# IF_TX.net
KiCad netlist of a schematic drawn in Altium Designer
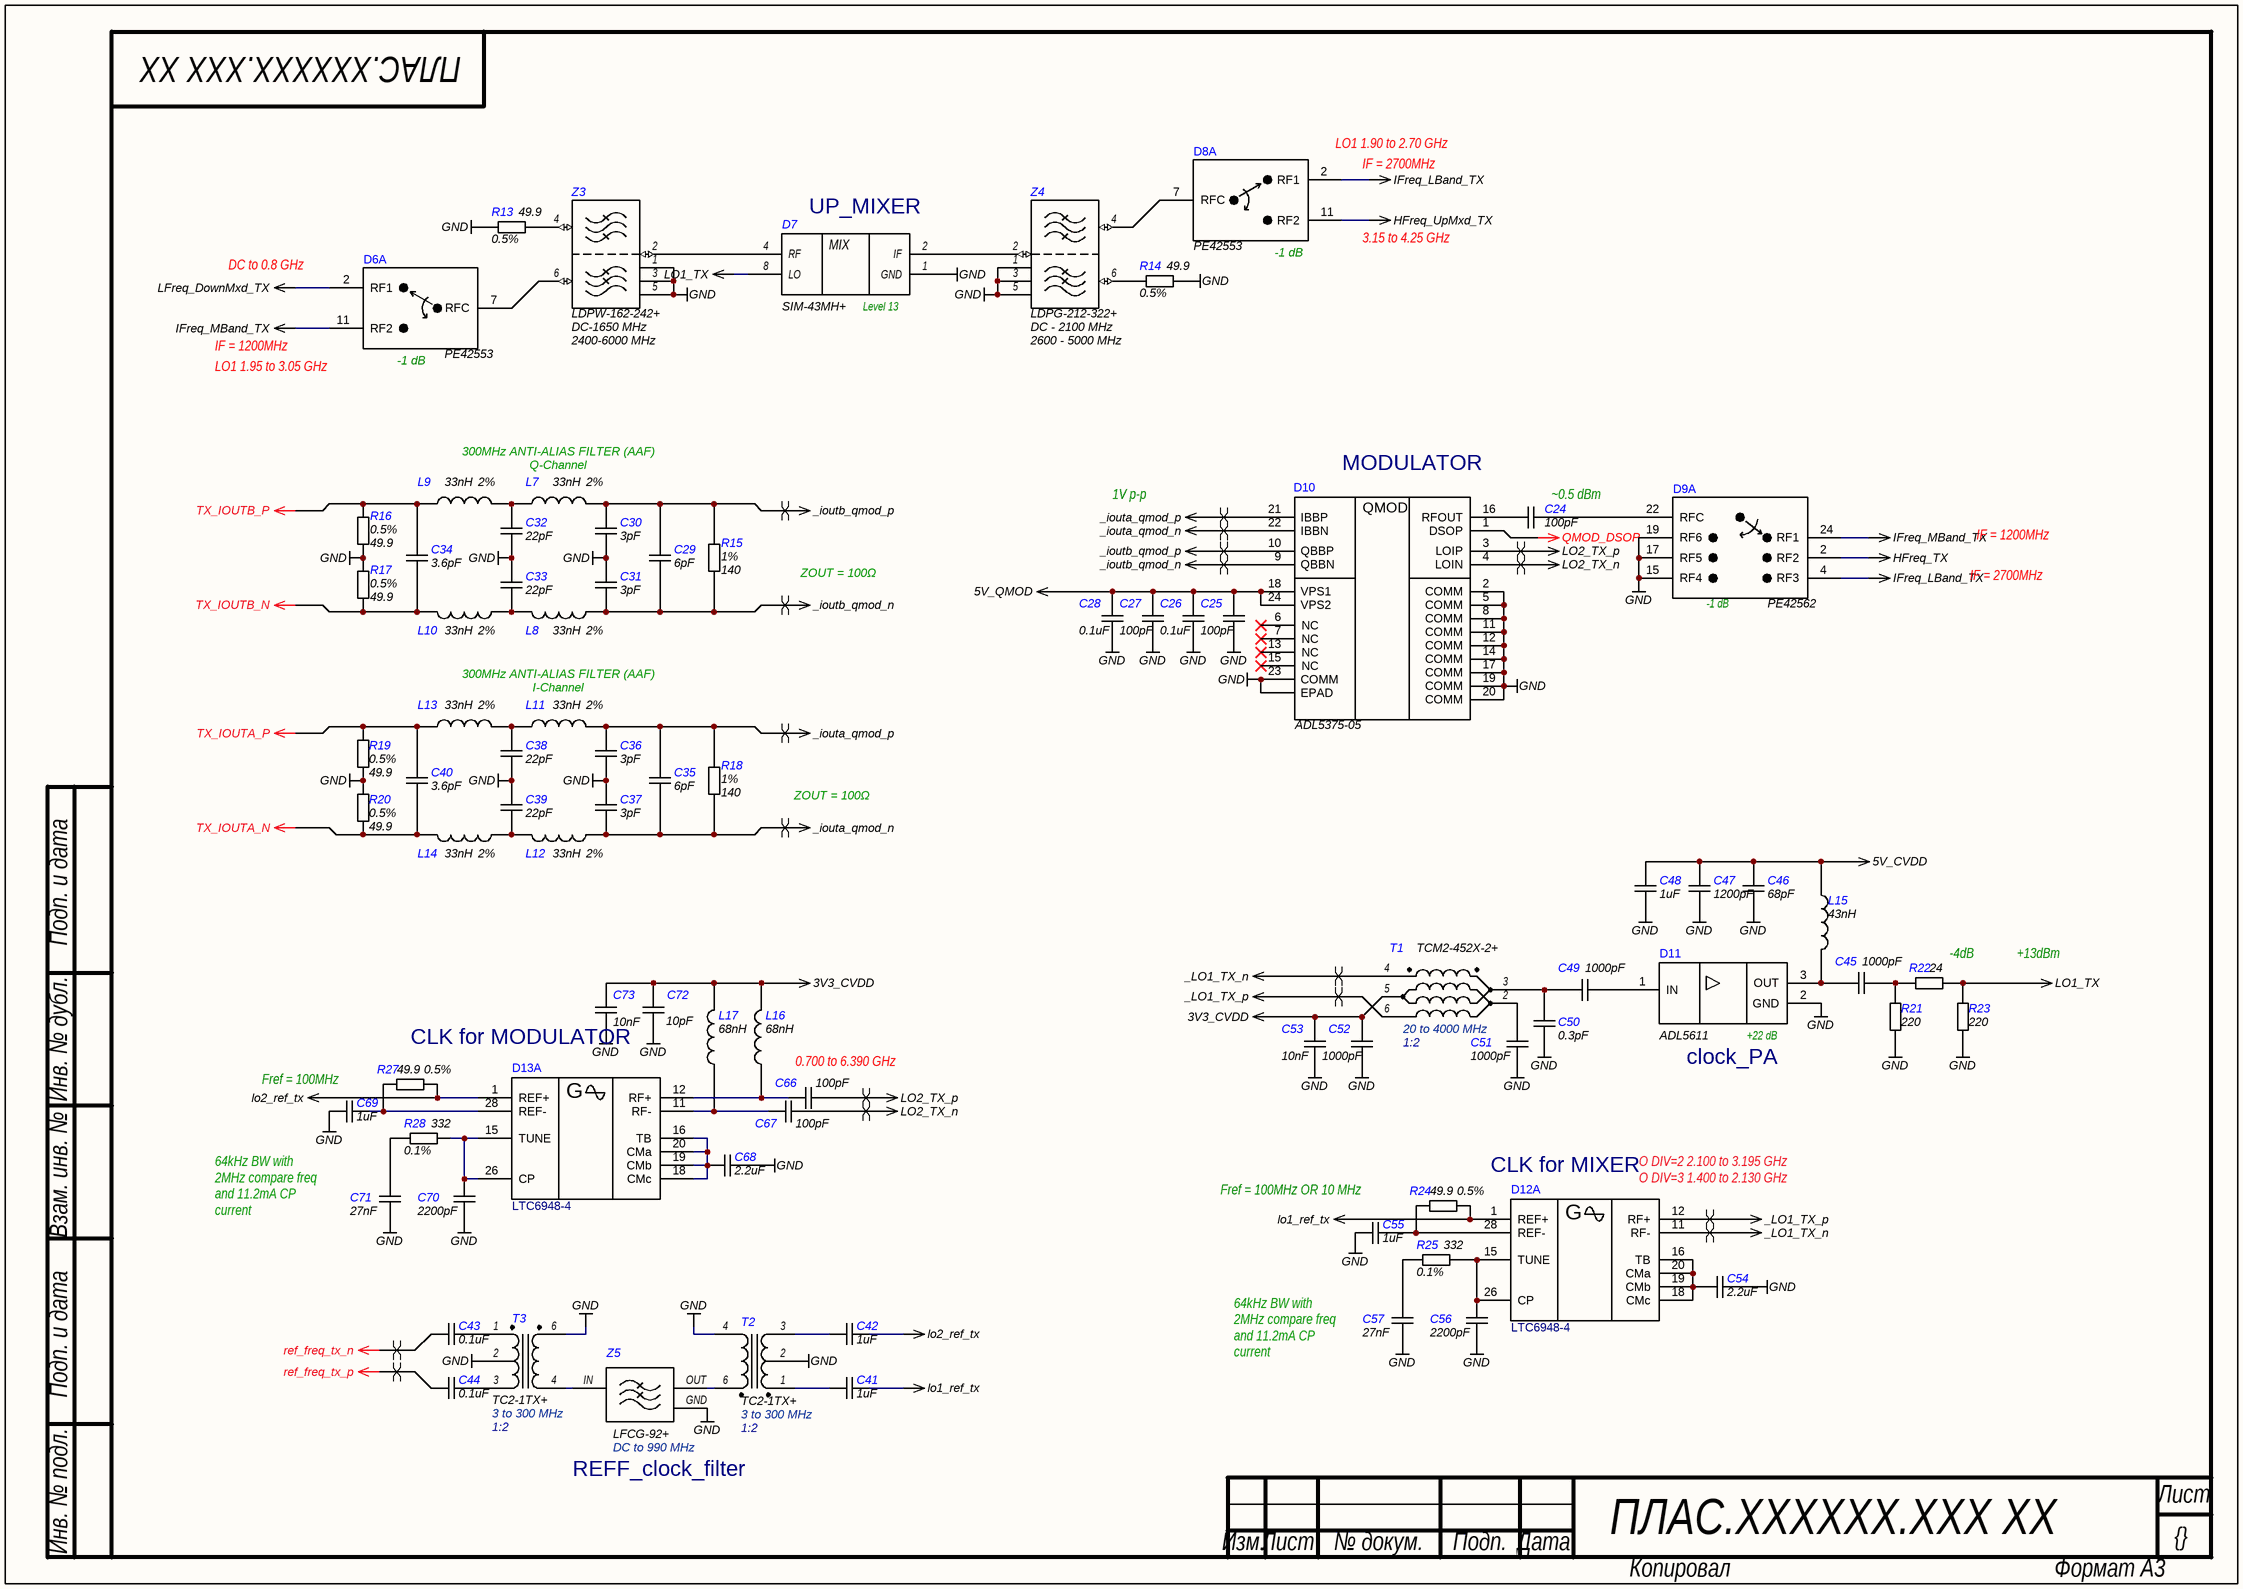
[diagram p0: IF_TX.SchDoc]

(export (version "E")
  (design (tool "Eeschema 10.0.6"))
  (components
    (comp (ref "C24")
      (value "100pF")
      (footprint "C0402")
      (description "SMD Capacitor")
      (fields (field (name "MANUFACTURER") "Murata") (field (name "TOLERANCE") "1%"))
      (libsource (lib "Kintex_SDR") (part "CAP"))
    )
    (comp (ref "C25")
      (value "100pF")
      (footprint "C0402")
      (description "SMD Capacitor")
      (fields (field (name "MANUFACTURER") "Murata") (field (name "TOLERANCE") "1%"))
      (libsource (lib "Kintex_SDR") (part "CAP"))
    )
    (comp (ref "C26")
      (value "0.1uF")
      (footprint "C0402")
      (description "SMD Capacitor")
      (fields (field (name "MANUFACTURER") "Murata") (field (name "TOLERANCE") "10%"))
      (libsource (lib "Kintex_SDR") (part "CAP"))
    )
    (comp (ref "C27")
      (value "100pF")
      (footprint "C0402")
      (description "SMD Capacitor")
      (fields (field (name "MANUFACTURER") "Murata") (field (name "TOLERANCE") "1%"))
      (libsource (lib "Kintex_SDR") (part "CAP"))
    )
    (comp (ref "C28")
      (value "0.1uF")
      (footprint "C0402")
      (description "SMD Capacitor")
      (fields (field (name "MANUFACTURER") "Murata") (field (name "TOLERANCE") "10%"))
      (libsource (lib "Kintex_SDR") (part "CAP"))
    )
    (comp (ref "C29")
      (value "6pF")
      (footprint "C0402")
      (description "SMD Capacitor")
      (fields (field (name "MANUFACTURER") "Murata") (field (name "TOLERANCE") "±0.5pF"))
      (libsource (lib "Kintex_SDR") (part "CAP"))
    )
    (comp (ref "C30")
      (value "3pF")
      (footprint "C0402")
      (description "SMD Capacitor")
      (fields (field (name "MANUFACTURER") "Murata") (field (name "TOLERANCE") "±0.25pF"))
      (libsource (lib "Kintex_SDR") (part "CAP"))
    )
    (comp (ref "C31")
      (value "3pF")
      (footprint "C0402")
      (description "SMD Capacitor")
      (fields (field (name "MANUFACTURER") "Murata") (field (name "TOLERANCE") "±0.25pF"))
      (libsource (lib "Kintex_SDR") (part "CAP"))
    )
    (comp (ref "C32")
      (value "22pF")
      (footprint "C0402")
      (description "SMD Capacitor")
      (fields (field (name "MANUFACTURER") "Murata") (field (name "TOLERANCE") "1%"))
      (libsource (lib "Kintex_SDR") (part "CAP"))
    )
    (comp (ref "C33")
      (value "22pF")
      (footprint "C0402")
      (description "SMD Capacitor")
      (fields (field (name "MANUFACTURER") "Murata") (field (name "TOLERANCE") "1%"))
      (libsource (lib "Kintex_SDR") (part "CAP"))
    )
    (comp (ref "C34")
      (value "3.6pF")
      (footprint "C0402")
      (description "SMD Capacitor")
      (fields (field (name "MANUFACTURER") "Murata") (field (name "TOLERANCE") "±0.25pF"))
      (libsource (lib "Kintex_SDR") (part "CAP"))
    )
    (comp (ref "C35")
      (value "6pF")
      (footprint "C0402")
      (description "SMD Capacitor")
      (fields (field (name "MANUFACTURER") "Murata") (field (name "TOLERANCE") "±0.5pF"))
      (libsource (lib "Kintex_SDR") (part "CAP"))
    )
    (comp (ref "C36")
      (value "3pF")
      (footprint "C0402")
      (description "SMD Capacitor")
      (fields (field (name "MANUFACTURER") "Murata") (field (name "TOLERANCE") "±0.25pF"))
      (libsource (lib "Kintex_SDR") (part "CAP"))
    )
    (comp (ref "C37")
      (value "3pF")
      (footprint "C0402")
      (description "SMD Capacitor")
      (fields (field (name "MANUFACTURER") "Murata") (field (name "TOLERANCE") "±0.25pF"))
      (libsource (lib "Kintex_SDR") (part "CAP"))
    )
    (comp (ref "C38")
      (value "22pF")
      (footprint "C0402")
      (description "SMD Capacitor")
      (fields (field (name "MANUFACTURER") "Murata") (field (name "TOLERANCE") "1%"))
      (libsource (lib "Kintex_SDR") (part "CAP"))
    )
    (comp (ref "C39")
      (value "22pF")
      (footprint "C0402")
      (description "SMD Capacitor")
      (fields (field (name "MANUFACTURER") "Murata") (field (name "TOLERANCE") "1%"))
      (libsource (lib "Kintex_SDR") (part "CAP"))
    )
    (comp (ref "C40")
      (value "3.6pF")
      (footprint "C0402")
      (description "SMD Capacitor")
      (fields (field (name "MANUFACTURER") "Murata") (field (name "TOLERANCE") "±0.25pF"))
      (libsource (lib "Kintex_SDR") (part "CAP"))
    )
    (comp (ref "C41")
      (value "1uF")
      (footprint "C0603")
      (description "SMD Capacitor")
      (fields (field (name "MANUFACTURER") "Kemet") (field (name "TOLERANCE") "10%"))
      (libsource (lib "Kintex_SDR") (part "CAP"))
    )
    (comp (ref "C42")
      (value "1uF")
      (footprint "C0603")
      (description "SMD Capacitor")
      (fields (field (name "MANUFACTURER") "Kemet") (field (name "TOLERANCE") "10%"))
      (libsource (lib "Kintex_SDR") (part "CAP"))
    )
    (comp (ref "C43")
      (value "0.1uF")
      (footprint "C0402")
      (description "SMD Capacitor")
      (fields (field (name "MANUFACTURER") "Murata") (field (name "TOLERANCE") "10%"))
      (libsource (lib "Kintex_SDR") (part "CAP"))
    )
    (comp (ref "C44")
      (value "0.1uF")
      (footprint "C0402")
      (description "SMD Capacitor")
      (fields (field (name "MANUFACTURER") "Murata") (field (name "TOLERANCE") "10%"))
      (libsource (lib "Kintex_SDR") (part "CAP"))
    )
    (comp (ref "C45")
      (value "1000pF")
      (footprint "C0402")
      (description "SMD Capacitor")
      (fields (field (name "MANUFACTURER") "Murata") (field (name "TOLERANCE") "5%"))
      (libsource (lib "Kintex_SDR") (part "CAP"))
    )
    (comp (ref "C46")
      (value "68pF")
      (footprint "C0402")
      (description "SMD Capacitor")
      (fields (field (name "MANUFACTURER") "Murata") (field (name "TOLERANCE") "±1%"))
      (libsource (lib "Kintex_SDR") (part "CAP"))
    )
    (comp (ref "C47")
      (value "1200pF")
      (footprint "C0603")
      (description "SMD Capacitor")
      (fields (field (name "MANUFACTURER") "Murata") (field (name "TOLERANCE") "±5%"))
      (libsource (lib "Kintex_SDR") (part "CAP"))
    )
    (comp (ref "C48")
      (value "1uF")
      (footprint "C0603")
      (description "SMD Capacitor")
      (fields (field (name "MANUFACTURER") "Kemet") (field (name "TOLERANCE") "10%"))
      (libsource (lib "Kintex_SDR") (part "CAP"))
    )
    (comp (ref "C49")
      (value "1000pF")
      (footprint "C0402")
      (description "SMD Capacitor")
      (fields (field (name "MANUFACTURER") "Murata") (field (name "TOLERANCE") "5%"))
      (libsource (lib "Kintex_SDR") (part "CAP"))
    )
    (comp (ref "C50")
      (value "0.3pF")
      (footprint "C0402")
      (description "SMD Capacitor")
      (fields (field (name "MANUFACTURER") "Murata") (field (name "TOLERANCE") "±0.05pF"))
      (libsource (lib "Kintex_SDR") (part "CAP"))
    )
    (comp (ref "C51")
      (value "1000pF")
      (footprint "C0402")
      (description "SMD Capacitor")
      (fields (field (name "MANUFACTURER") "Murata") (field (name "TOLERANCE") "5%"))
      (libsource (lib "Kintex_SDR") (part "CAP"))
    )
    (comp (ref "C52")
      (value "1000pF")
      (footprint "C0402")
      (description "SMD Capacitor")
      (fields (field (name "MANUFACTURER") "Murata") (field (name "TOLERANCE") "5%"))
      (libsource (lib "Kintex_SDR") (part "CAP"))
    )
    (comp (ref "C53")
      (value "10nF")
      (footprint "C0402")
      (description "SMD Capacitor")
      (fields (field (name "MANUFACTURER") "Murata") (field (name "TOLERANCE") "10%"))
      (libsource (lib "Kintex_SDR") (part "CAP"))
    )
    (comp (ref "C54")
      (value "2.2uF")
      (footprint "C0603")
      (description "SMD Capacitor")
      (fields (field (name "MANUFACTURER") "Murata") (field (name "TOLERANCE") "10%"))
      (libsource (lib "Kintex_SDR") (part "CAP"))
    )
    (comp (ref "C55")
      (value "1uF")
      (footprint "C0603")
      (description "SMD Capacitor")
      (fields (field (name "MANUFACTURER") "Kemet") (field (name "TOLERANCE") "10%"))
      (libsource (lib "Kintex_SDR") (part "CAP"))
    )
    (comp (ref "C56")
      (value "2200pF")
      (footprint "C0603")
      (description "SMD Capacitor")
      (fields (field (name "MANUFACTURER") "Kemet") (field (name "TOLERANCE") "1%"))
      (libsource (lib "Kintex_SDR") (part "CAP"))
    )
    (comp (ref "C57")
      (value "27nF")
      (footprint "C0603")
      (description "SMD Capacitor")
      (fields (field (name "MANUFACTURER") "KYOCERA AVX") (field (name "TOLERANCE") "±5%"))
      (libsource (lib "Kintex_SDR") (part "CAP"))
    )
    (comp (ref "C66")
      (value "100pF")
      (footprint "C0402")
      (description "SMD Capacitor")
      (fields (field (name "MANUFACTURER") "Murata") (field (name "TOLERANCE") "1%"))
      (libsource (lib "Kintex_SDR") (part "CAP"))
    )
    (comp (ref "C67")
      (value "100pF")
      (footprint "C0402")
      (description "SMD Capacitor")
      (fields (field (name "MANUFACTURER") "Murata") (field (name "TOLERANCE") "1%"))
      (libsource (lib "Kintex_SDR") (part "CAP"))
    )
    (comp (ref "C68")
      (value "2.2uF")
      (footprint "C0603")
      (description "SMD Capacitor")
      (fields (field (name "MANUFACTURER") "Murata") (field (name "TOLERANCE") "10%"))
      (libsource (lib "Kintex_SDR") (part "CAP"))
    )
    (comp (ref "C69")
      (value "1uF")
      (footprint "C0603")
      (description "SMD Capacitor")
      (fields (field (name "MANUFACTURER") "Kemet") (field (name "TOLERANCE") "10%"))
      (libsource (lib "Kintex_SDR") (part "CAP"))
    )
    (comp (ref "C70")
      (value "2200pF")
      (footprint "C0603")
      (description "SMD Capacitor")
      (fields (field (name "MANUFACTURER") "Kemet") (field (name "TOLERANCE") "1%"))
      (libsource (lib "Kintex_SDR") (part "CAP"))
    )
    (comp (ref "C71")
      (value "27nF")
      (footprint "C0603")
      (description "SMD Capacitor")
      (fields (field (name "MANUFACTURER") "KYOCERA AVX") (field (name "TOLERANCE") "±5%"))
      (libsource (lib "Kintex_SDR") (part "CAP"))
    )
    (comp (ref "C72")
      (value "10pF")
      (footprint "C0402")
      (description "SMD Capacitor")
      (fields (field (name "MANUFACTURER") "Murata") (field (name "TOLERANCE") "1%"))
      (libsource (lib "Kintex_SDR") (part "CAP"))
    )
    (comp (ref "C73")
      (value "10nF")
      (footprint "C0402")
      (description "SMD Capacitor")
      (fields (field (name "MANUFACTURER") "Murata") (field (name "TOLERANCE") "10%"))
      (libsource (lib "Kintex_SDR") (part "CAP"))
    )
    (comp (ref "D6")
      (value "PE42553")
      (footprint "QFN-16")
      (description "HaRPTM technology-enhanced absorptive SPDT")
      (fields (field (name "MANUFACTURER") "Peregrine Technical Solutions"))
      (libsource (lib "DBLib") (part "PE42553"))
    )
    (comp (ref "D7")
      (value "SIM-43MH+")
      (footprint "DBLib:SIM-43MH+")
      (description "Frequency Mixer")
      (fields (field (name "MANUFACTURER") "Mini-Circuits"))
      (libsource (lib "DBLib") (part "SIM-43MH+"))
    )
    (comp (ref "D8")
      (value "PE42553")
      (footprint "QFN-16")
      (description "HaRPTM technology-enhanced absorptive SPDT")
      (fields (field (name "MANUFACTURER") "Peregrine Technical Solutions"))
      (libsource (lib "") (part "PE42553_1"))
    )
    (comp (ref "D9")
      (value "PE42562")
      (footprint "QFN-24")
      (description "The PE42582 is a HaRP™ technology-enhanced absorptive SP6T RF switch")
      (fields (field (name "MANUFACTURER") "Peregrine Technical Solutions"))
      (libsource (lib "DBLib") (part "PE42562"))
    )
    (comp (ref "D10")
      (value "ADL5375")
      (footprint "LFCSP-24")
      (description "Broadband Quadrature Modulator")
      (fields
        (field (name "MANUFACTURER") "Analog Devices")
        (field (name "VOLTAGE") "4.75 V to 5.25 V")
        (field (name "NAME") "ADL5375-05")
      )
      (libsource (lib "DBLib") (part "ADL5375"))
    )
    (comp (ref "D11")
      (value "ADL5611")
      (footprint "DBLib:ADL5610")
      (description "RF/IF Gain Block")
      (fields (field (name "MANUFACTURER") "Analog Devices"))
      (libsource (lib "DBLib") (part "ADL5611"))
    )
    (comp (ref "D12")
      (value "LTC6948-4")
      (footprint "QFN-28")
      (description "The LTC®LTC6948 is a high performance, low noise, 6.39GHz  phase-locked loop (PLL)")
      (fields (field (name "MANUFACTURER") "Linear Technology") (field (name "VOLTAGE") "3.15 V ~ 5.25 V"))
      (libsource (lib "DBLib") (part "LTC6948"))
    )
    (comp (ref "D13")
      (value "LTC6948-4")
      (footprint "QFN-28")
      (description "The LTC®LTC6948 is a high performance, low noise, 6.39GHz  phase-locked loop (PLL)")
      (fields (field (name "MANUFACTURER") "Linear Technology") (field (name "VOLTAGE") "3.15 V ~ 5.25 V"))
      (libsource (lib "DBLib") (part "LTC6948"))
    )
    (comp (ref "L7")
      (value "33nH")
      (footprint "DBLib:L0603_HP")
      (description "Chip SMD Inductor")
      (fields
        (field (name "MANUFACTURER") "Coilcraft")
        (field (name "TOLERANCE") "2%")
        (field (name "Comment") "Inductor RF")
      )
      (libsource (lib "") (part "Inductor RF_1"))
    )
    (comp (ref "L8")
      (value "33nH")
      (footprint "DBLib:L0603_HP")
      (description "Chip SMD Inductor")
      (fields
        (field (name "MANUFACTURER") "Coilcraft")
        (field (name "TOLERANCE") "2%")
        (field (name "Comment") "Inductor RF")
      )
      (libsource (lib "DBLib") (part "Inductor RF"))
    )
    (comp (ref "L9")
      (value "33nH")
      (footprint "DBLib:L0603_HP")
      (description "Chip SMD Inductor")
      (fields
        (field (name "MANUFACTURER") "Coilcraft")
        (field (name "TOLERANCE") "2%")
        (field (name "Comment") "Inductor RF")
      )
      (libsource (lib "") (part "Inductor RF_1"))
    )
    (comp (ref "L10")
      (value "33nH")
      (footprint "DBLib:L0603_HP")
      (description "Chip SMD Inductor")
      (fields
        (field (name "MANUFACTURER") "Coilcraft")
        (field (name "TOLERANCE") "2%")
        (field (name "Comment") "Inductor RF")
      )
      (libsource (lib "DBLib") (part "Inductor RF"))
    )
    (comp (ref "L11")
      (value "33nH")
      (footprint "DBLib:L0603_HP")
      (description "Chip SMD Inductor")
      (fields
        (field (name "MANUFACTURER") "Coilcraft")
        (field (name "TOLERANCE") "2%")
        (field (name "Comment") "Inductor RF")
      )
      (libsource (lib "") (part "Inductor RF_1"))
    )
    (comp (ref "L12")
      (value "33nH")
      (footprint "DBLib:L0603_HP")
      (description "Chip SMD Inductor")
      (fields
        (field (name "MANUFACTURER") "Coilcraft")
        (field (name "TOLERANCE") "2%")
        (field (name "Comment") "Inductor RF")
      )
      (libsource (lib "DBLib") (part "Inductor RF"))
    )
    (comp (ref "L13")
      (value "33nH")
      (footprint "DBLib:L0603_HP")
      (description "Chip SMD Inductor")
      (fields
        (field (name "MANUFACTURER") "Coilcraft")
        (field (name "TOLERANCE") "2%")
        (field (name "Comment") "Inductor RF")
      )
      (libsource (lib "") (part "Inductor RF_1"))
    )
    (comp (ref "L14")
      (value "33nH")
      (footprint "DBLib:L0603_HP")
      (description "Chip SMD Inductor")
      (fields
        (field (name "MANUFACTURER") "Coilcraft")
        (field (name "TOLERANCE") "2%")
        (field (name "Comment") "Inductor RF")
      )
      (libsource (lib "DBLib") (part "Inductor RF"))
    )
    (comp (ref "L15")
      (value "43nH")
      (footprint "DBLib:L0603_HP")
      (description "Chip SMD Inductor")
      (fields (field (name "MANUFACTURER") "Coilcraft") (field (name "TOLERANCE") "5%"))
      (libsource (lib "DBLib") (part "Inductor RF"))
    )
    (comp (ref "L16")
      (value "68nH")
      (footprint "DBLib:L0603_HP")
      (description "Chip SMD Inductor")
      (fields (field (name "MANUFACTURER") "Coilcraft") (field (name "TOLERANCE") "5%"))
      (libsource (lib "") (part "Inductor RF_1"))
    )
    (comp (ref "L17")
      (value "68nH")
      (footprint "DBLib:L0603_HP")
      (description "Chip SMD Inductor")
      (fields (field (name "MANUFACTURER") "Coilcraft") (field (name "TOLERANCE") "5%"))
      (libsource (lib "") (part "Inductor RF_1"))
    )
    (comp (ref "R13")
      (value "49.9")
      (footprint "R0402")
      (description "SMD Resistor")
      (fields
        (field (name "POWER") "0.063 Wt")
        (field (name "TOLERANCE") "0.5%")
        (field (name "MANUFACTURER") "Panasonic Electronic Components")
      )
      (libsource (lib "") (part "RES_2"))
    )
    (comp (ref "R14")
      (value "49.9")
      (footprint "R0402")
      (description "SMD Resistor")
      (fields
        (field (name "POWER") "0.063 Wt")
        (field (name "TOLERANCE") "0.5%")
        (field (name "MANUFACTURER") "Panasonic Electronic Components")
      )
      (libsource (lib "") (part "RES_1"))
    )
    (comp (ref "R15")
      (value "140")
      (footprint "R0402")
      (description "SMD Resistor")
      (fields
        (field (name "POWER") "0.1 Wt")
        (field (name "TOLERANCE") "1%")
        (field (name "MANUFACTURER") "Panasonic Electronic Components")
      )
      (libsource (lib "") (part "RES_1"))
    )
    (comp (ref "R16")
      (value "49.9")
      (footprint "R0402")
      (description "SMD Resistor")
      (fields
        (field (name "POWER") "0.063 Wt")
        (field (name "TOLERANCE") "0.5%")
        (field (name "MANUFACTURER") "Panasonic Electronic Components")
      )
      (libsource (lib "") (part "RES_1"))
    )
    (comp (ref "R17")
      (value "49.9")
      (footprint "R0402")
      (description "SMD Resistor")
      (fields
        (field (name "POWER") "0.063 Wt")
        (field (name "TOLERANCE") "0.5%")
        (field (name "MANUFACTURER") "Panasonic Electronic Components")
      )
      (libsource (lib "") (part "RES_1"))
    )
    (comp (ref "R18")
      (value "140")
      (footprint "R0402")
      (description "SMD Resistor")
      (fields
        (field (name "POWER") "0.1 Wt")
        (field (name "TOLERANCE") "1%")
        (field (name "MANUFACTURER") "Panasonic Electronic Components")
      )
      (libsource (lib "") (part "RES_1"))
    )
    (comp (ref "R19")
      (value "49.9")
      (footprint "R0402")
      (description "SMD Resistor")
      (fields
        (field (name "POWER") "0.063 Wt")
        (field (name "TOLERANCE") "0.5%")
        (field (name "MANUFACTURER") "Panasonic Electronic Components")
      )
      (libsource (lib "") (part "RES_1"))
    )
    (comp (ref "R20")
      (value "49.9")
      (footprint "R0402")
      (description "SMD Resistor")
      (fields
        (field (name "POWER") "0.063 Wt")
        (field (name "TOLERANCE") "0.5%")
        (field (name "MANUFACTURER") "Panasonic Electronic Components")
      )
      (libsource (lib "") (part "RES_1"))
    )
    (comp (ref "R21")
      (value "220")
      (footprint "R0402")
      (description "SMD Resistor")
      (fields (field (name "POWER") "0.1 Wt") (field (name "TOLERANCE") "±1%"))
      (libsource (lib "Kintex_SDR") (part "RES"))
    )
    (comp (ref "R22")
      (value "24")
      (footprint "R0402")
      (description "SMD Resistor")
      (fields (field (name "POWER") "0.063 Wt") (field (name "TOLERANCE") "±1%"))
      (libsource (lib "") (part "RES_1"))
    )
    (comp (ref "R23")
      (value "220")
      (footprint "R0402")
      (description "SMD Resistor")
      (fields (field (name "POWER") "0.1 Wt") (field (name "TOLERANCE") "±1%"))
      (libsource (lib "Kintex_SDR") (part "RES"))
    )
    (comp (ref "R24")
      (value "49.9")
      (footprint "R0402")
      (description "SMD Resistor")
      (fields
        (field (name "POWER") "0.063 Wt")
        (field (name "TOLERANCE") "0.5%")
        (field (name "MANUFACTURER") "Panasonic Electronic Components")
      )
      (libsource (lib "") (part "RES_1"))
    )
    (comp (ref "R25")
      (value "332")
      (footprint "R0603")
      (description "SMD Resistor")
      (fields
        (field (name "POWER") "0.1 Wt")
        (field (name "TOLERANCE") "0.1%")
        (field (name "MANUFACTURER") "Panasonic Electronic Components")
      )
      (libsource (lib "") (part "RES_1"))
    )
    (comp (ref "R27")
      (value "49.9")
      (footprint "R0402")
      (description "SMD Resistor")
      (fields
        (field (name "POWER") "0.063 Wt")
        (field (name "TOLERANCE") "0.5%")
        (field (name "MANUFACTURER") "Panasonic Electronic Components")
      )
      (libsource (lib "") (part "RES_1"))
    )
    (comp (ref "R28")
      (value "332")
      (footprint "R0603")
      (description "SMD Resistor")
      (fields
        (field (name "POWER") "0.1 Wt")
        (field (name "TOLERANCE") "0.1%")
        (field (name "MANUFACTURER") "Panasonic Electronic Components")
      )
      (libsource (lib "") (part "RES_1"))
    )
    (comp (ref "T1")
      (value "TCM2-452X-2+")
      (footprint "DB1627")
      (description "RF Transformer")
      (fields
        (field (name "MANUFACTURER") "Mini-Circuits")
        (field (name "FREQUENCY") "20 to 4000 MHz")
        (field (name "RATIO") "1:2")
      )
      (libsource (lib "DBLib") (part "TCM2-452X-2+"))
    )
    (comp (ref "T2")
      (value "TC2-1TX+")
      (footprint "DBLib:AT1521")
      (description "RF Transformer")
      (fields
        (field (name "MANUFACTURER") "Mini-Circuits")
        (field (name "FREQUENCY") "3 to 300 MHz")
        (field (name "RATIO") "1:2")
      )
      (libsource (lib "DBLib") (part "TC2-1TX+"))
    )
    (comp (ref "T3")
      (value "TC2-1TX+")
      (footprint "DBLib:AT1521")
      (description "RF Transformer")
      (fields
        (field (name "MANUFACTURER") "Mini-Circuits")
        (field (name "FREQUENCY") "3 to 300 MHz")
        (field (name "RATIO") "1:2")
      )
      (libsource (lib "DBLib") (part "TC2-1TX+"))
    )
    (comp (ref "Z3")
      (value "LDPW-162-242+")
      (footprint "DBLib:JC0603C")
      (description "Diplexer")
      (fields
        (field (name "MANUFACTURER") "Mini-Circuits")
        (field (name "LOW PASS") "DC-1650 MHz")
        (field (name "HIGH PASS") "2400-6000 MHz")
      )
      (libsource (lib "DBLib") (part "LDPW-162-242+"))
    )
    (comp (ref "Z4")
      (value "LDPG-212-322+")
      (footprint "GE0805C-10")
      (description "Diplexer")
      (fields
        (field (name "MANUFACTURER") "Mini-Circuits")
        (field (name "LOW PASS") "DC - 2100 MHz")
        (field (name "HIGH PASS") "2600 - 5000 MHz")
      )
      (libsource (lib "DBLib") (part "LDPG-212-322+"))
    )
    (comp (ref "Z5")
      (value "LFCG-92+")
      (footprint "GE0805C-2")
      (description "Low Pass Filter")
      (fields (field (name "MANUFACTURER") "Mini-Circuits") (field (name "FREQUENCY") "DC to 990 MHz"))
      (libsource (lib "DBLib") (part "LFCG-92+"))
    )
  )
  (nets
    (net (code "1") (name "3V3_CVDD") (class "Default")
      (node (ref "C52") (pin "1") (pinfunction "1_1") (pintype "passive"))
      (node (ref "C53") (pin "2") (pinfunction "2_2") (pintype "passive"))
      (node (ref "C72") (pin "2") (pinfunction "2_2") (pintype "passive"))
      (node (ref "C73") (pin "2") (pinfunction "2_2") (pintype "passive"))
      (node (ref "L16") (pin "2") (pinfunction "2_2") (pintype "passive"))
      (node (ref "L17") (pin "2") (pinfunction "2_2") (pintype "passive"))
      (node (ref "T1") (pin "5") (pinfunction "5_5") (pintype "passive"))
    )
    (net (code "2") (name "5V_CVDD") (class "Default")
      (node (ref "C46") (pin "2") (pinfunction "2_2") (pintype "passive"))
      (node (ref "C47") (pin "2") (pinfunction "2_2") (pintype "passive"))
      (node (ref "C48") (pin "1") (pinfunction "1_1") (pintype "passive"))
      (node (ref "L15") (pin "2") (pinfunction "2_2") (pintype "passive"))
    )
    (net (code "3") (name "5V_QMOD") (class "Default")
      (node (ref "C25") (pin "2") (pinfunction "2_2") (pintype "passive"))
      (node (ref "C26") (pin "2") (pinfunction "2_2") (pintype "passive"))
      (node (ref "C27") (pin "2") (pinfunction "2_2") (pintype "passive"))
      (node (ref "C28") (pin "2") (pinfunction "2_2") (pintype "passive"))
      (node (ref "D10") (pin "18") (pinfunction "VPS1_18") (pintype "passive"))
      (node (ref "D10") (pin "24") (pinfunction "VPS2_24") (pintype "passive"))
    )
    (net (code "4") (name "GND") (class "Default")
      (node (ref "C25") (pin "1") (pinfunction "1_1") (pintype "passive"))
      (node (ref "C26") (pin "1") (pinfunction "1_1") (pintype "passive"))
      (node (ref "C27") (pin "1") (pinfunction "1_1") (pintype "passive"))
      (node (ref "C28") (pin "1") (pinfunction "1_1") (pintype "passive"))
      (node (ref "C30") (pin "2") (pinfunction "2_2") (pintype "passive"))
      (node (ref "C31") (pin "1") (pinfunction "1_1") (pintype "passive"))
      (node (ref "C32") (pin "2") (pinfunction "2_2") (pintype "passive"))
      (node (ref "C33") (pin "1") (pinfunction "1_1") (pintype "passive"))
      (node (ref "C36") (pin "2") (pinfunction "2_2") (pintype "passive"))
      (node (ref "C37") (pin "1") (pinfunction "1_1") (pintype "passive"))
      (node (ref "C38") (pin "2") (pinfunction "2_2") (pintype "passive"))
      (node (ref "C39") (pin "1") (pinfunction "1_1") (pintype "passive"))
      (node (ref "C46") (pin "1") (pinfunction "1_1") (pintype "passive"))
      (node (ref "C47") (pin "1") (pinfunction "1_1") (pintype "passive"))
      (node (ref "C48") (pin "2") (pinfunction "2_2") (pintype "passive"))
      (node (ref "C50") (pin "1") (pinfunction "1_1") (pintype "passive"))
      (node (ref "C51") (pin "2") (pinfunction "2_2") (pintype "passive"))
      (node (ref "C52") (pin "2") (pinfunction "2_2") (pintype "passive"))
      (node (ref "C53") (pin "1") (pinfunction "1_1") (pintype "passive"))
      (node (ref "C54") (pin "1") (pinfunction "1_1") (pintype "passive"))
      (node (ref "C55") (pin "2") (pinfunction "2_2") (pintype "passive"))
      (node (ref "C56") (pin "1") (pinfunction "1_1") (pintype "passive"))
      (node (ref "C57") (pin "1") (pinfunction "1_1") (pintype "passive"))
      (node (ref "C68") (pin "1") (pinfunction "1_1") (pintype "passive"))
      (node (ref "C69") (pin "2") (pinfunction "2_2") (pintype "passive"))
      (node (ref "C70") (pin "1") (pinfunction "1_1") (pintype "passive"))
      (node (ref "C71") (pin "1") (pinfunction "1_1") (pintype "passive"))
      (node (ref "C72") (pin "1") (pinfunction "1_1") (pintype "passive"))
      (node (ref "C73") (pin "1") (pinfunction "1_1") (pintype "passive"))
      (node (ref "D10") (pin "11") (pinfunction "COMM_11") (pintype "passive"))
      (node (ref "D10") (pin "12") (pinfunction "COMM_12") (pintype "passive"))
      (node (ref "D10") (pin "14") (pinfunction "COMM_14") (pintype "passive"))
      (node (ref "D10") (pin "17") (pinfunction "COMM_17") (pintype "passive"))
      (node (ref "D10") (pin "19") (pinfunction "COMM_19") (pintype "passive"))
      (node (ref "D10") (pin "2") (pinfunction "COMM_2") (pintype "passive"))
      (node (ref "D10") (pin "20") (pinfunction "COMM_20") (pintype "passive"))
      (node (ref "D10") (pin "23") (pinfunction "COMM_23") (pintype "passive"))
      (node (ref "D10") (pin "25") (pinfunction "EPAD_25") (pintype "passive"))
      (node (ref "D10") (pin "5") (pinfunction "COMM_5") (pintype "passive"))
      (node (ref "D10") (pin "8") (pinfunction "COMM_8") (pintype "passive"))
      (node (ref "D11") (pin "2") (pinfunction "GND_2") (pintype "passive"))
      (node (ref "D7") (pin "1") (pinfunction "GND_1") (pintype "passive"))
      (node (ref "D9") (pin "15") (pinfunction "RF4_15") (pintype "passive"))
      (node (ref "D9") (pin "17") (pinfunction "RF5_17") (pintype "passive"))
      (node (ref "D9") (pin "19") (pinfunction "RF6_19") (pintype "passive"))
      (node (ref "R13") (pin "1") (pinfunction "1_1") (pintype "passive"))
      (node (ref "R14") (pin "1") (pinfunction "1_1") (pintype "passive"))
      (node (ref "R16") (pin "2") (pinfunction "2_2") (pintype "passive"))
      (node (ref "R17") (pin "1") (pinfunction "1_1") (pintype "passive"))
      (node (ref "R19") (pin "2") (pinfunction "2_2") (pintype "passive"))
      (node (ref "R20") (pin "1") (pinfunction "1_1") (pintype "passive"))
      (node (ref "R21") (pin "2") (pinfunction "2_2") (pintype "passive"))
      (node (ref "R23") (pin "2") (pinfunction "2_2") (pintype "passive"))
      (node (ref "T2") (pin "2") (pinfunction "2_2") (pintype "passive"))
      (node (ref "T2") (pin "4") (pinfunction "4_4") (pintype "passive"))
      (node (ref "T3") (pin "2") (pinfunction "2_2") (pintype "passive"))
      (node (ref "T3") (pin "6") (pinfunction "6_6") (pintype "passive"))
      (node (ref "Z3") (pin "1") (pinfunction "GND_1") (pintype "passive"))
      (node (ref "Z3") (pin "3") (pinfunction "GND_3") (pintype "passive"))
      (node (ref "Z3") (pin "5") (pinfunction "GND_5") (pintype "passive"))
      (node (ref "Z4") (pin "1") (pinfunction "GND_1") (pintype "passive"))
      (node (ref "Z4") (pin "3") (pinfunction "GND_3") (pintype "passive"))
      (node (ref "Z4") (pin "5") (pinfunction "GND_5") (pintype "passive"))
      (node (ref "Z5") (pin "GND") (pinfunction "GND_GND") (pintype "passive"))
    )
    (net (code "5") (name "HFreq_TX") (class "Default")
      (node (ref "D9") (pin "2") (pinfunction "RF2_2") (pintype "passive"))
    )
    (net (code "6") (name "HFreq_UpMxd_TX") (class "Default")
      (node (ref "D8") (pin "11") (pinfunction "RF2_11") (pintype "passive"))
    )
    (net (code "7") (name "IFreq_LBand_TX") (class "Default")
      (node (ref "D8") (pin "2") (pinfunction "RF1_2") (pintype "passive"))
      (node (ref "D9") (pin "4") (pinfunction "RF3_4") (pintype "passive"))
    )
    (net (code "8") (name "IFreq_MBand_TX") (class "Default")
      (node (ref "D6") (pin "11") (pinfunction "RF2_11") (pintype "passive"))
      (node (ref "D9") (pin "24") (pinfunction "RF1_24") (pintype "passive"))
    )
    (net (code "9") (name "LFreq_DownMxd_TX") (class "Default")
      (node (ref "D6") (pin "2") (pinfunction "RF1_2") (pintype "passive"))
    )
    (net (code "10") (name "LO1_TX") (class "Default")
      (node (ref "D7") (pin "8") (pinfunction "LO_8") (pintype "passive"))
      (node (ref "R22") (pin "1") (pinfunction "1_1") (pintype "passive"))
      (node (ref "R23") (pin "1") (pinfunction "1_1") (pintype "passive"))
    )
    (net (code "11") (name "LO2_TX_n") (class "Default")
      (node (ref "C67") (pin "2") (pinfunction "2_2") (pintype "passive"))
      (node (ref "D10") (pin "4") (pinfunction "LOIN_4") (pintype "passive"))
    )
    (net (code "12") (name "LO2_TX_p") (class "Default")
      (node (ref "C66") (pin "2") (pinfunction "2_2") (pintype "passive"))
      (node (ref "D10") (pin "3") (pinfunction "LOIP_3") (pintype "passive"))
    )
    (net (code "13") (name "Net-(C32-Pad1)") (class "Default")
      (node (ref "C32") (pin "1") (pinfunction "1_1") (pintype "passive"))
      (node (ref "L7") (pin "1") (pinfunction "1_1") (pintype "passive"))
      (node (ref "L9") (pin "2") (pinfunction "2_2") (pintype "passive"))
    )
    (net (code "14") (name "Net-(C33-Pad2)") (class "Default")
      (node (ref "C33") (pin "2") (pinfunction "2_2") (pintype "passive"))
      (node (ref "L10") (pin "2") (pinfunction "2_2") (pintype "passive"))
      (node (ref "L8") (pin "1") (pinfunction "1_1") (pintype "passive"))
    )
    (net (code "15") (name "Net-(C38-Pad1)") (class "Default")
      (node (ref "C38") (pin "1") (pinfunction "1_1") (pintype "passive"))
      (node (ref "L11") (pin "1") (pinfunction "1_1") (pintype "passive"))
      (node (ref "L13") (pin "2") (pinfunction "2_2") (pintype "passive"))
    )
    (net (code "16") (name "Net-(C39-Pad2)") (class "Default")
      (node (ref "C39") (pin "2") (pinfunction "2_2") (pintype "passive"))
      (node (ref "L12") (pin "1") (pinfunction "1_1") (pintype "passive"))
      (node (ref "L14") (pin "2") (pinfunction "2_2") (pintype "passive"))
    )
    (net (code "17") (name "Net-(C41-Pad2)") (class "Default")
      (node (ref "C41") (pin "2") (pinfunction "2_2") (pintype "passive"))
      (node (ref "T2") (pin "1") (pinfunction "1_1") (pintype "passive"))
    )
    (net (code "18") (name "Net-(C42-Pad2)") (class "Default")
      (node (ref "C42") (pin "2") (pinfunction "2_2") (pintype "passive"))
      (node (ref "T2") (pin "3") (pinfunction "3_3") (pintype "passive"))
    )
    (net (code "19") (name "Net-(C43-Pad1)") (class "Default")
      (node (ref "C43") (pin "1") (pinfunction "1_1") (pintype "passive"))
      (node (ref "T3") (pin "1") (pinfunction "1_1") (pintype "passive"))
    )
    (net (code "20") (name "Net-(C44-Pad1)") (class "Default")
      (node (ref "C44") (pin "1") (pinfunction "1_1") (pintype "passive"))
      (node (ref "T3") (pin "3") (pinfunction "3_3") (pintype "passive"))
    )
    (net (code "21") (name "Net-(C45-Pad2)") (class "Default")
      (node (ref "C45") (pin "2") (pinfunction "2_2") (pintype "passive"))
      (node (ref "R21") (pin "1") (pinfunction "1_1") (pintype "passive"))
      (node (ref "R22") (pin "2") (pinfunction "2_2") (pintype "passive"))
    )
    (net (code "22") (name "Net-(C49-Pad1)") (class "Default")
      (node (ref "C49") (pin "1") (pinfunction "1_1") (pintype "passive"))
      (node (ref "C50") (pin "2") (pinfunction "2_2") (pintype "passive"))
      (node (ref "T1") (pin "3") (pinfunction "3_3") (pintype "passive"))
    )
    (net (code "23") (name "Net-(C51-Pad1)") (class "Default")
      (node (ref "C51") (pin "1") (pinfunction "1_1") (pintype "passive"))
      (node (ref "T1") (pin "2") (pinfunction "2_2") (pintype "passive"))
    )
    (net (code "24") (name "Net-(C57-Pad2)") (class "Default")
      (node (ref "C57") (pin "2") (pinfunction "2_2") (pintype "passive"))
      (node (ref "R25") (pin "2") (pinfunction "2_2") (pintype "passive"))
    )
    (net (code "25") (name "Net-(C71-Pad2)") (class "Default")
      (node (ref "C71") (pin "2") (pinfunction "2_2") (pintype "passive"))
      (node (ref "R28") (pin "2") (pinfunction "2_2") (pintype "passive"))
    )
    (net (code "26") (name "Net-(D6A-RFC)") (class "Default")
      (node (ref "D6") (pin "7") (pinfunction "RFC_7") (pintype "passive"))
      (node (ref "Z3") (pin "6") (pinfunction "6_6") (pintype "bidirectional"))
    )
    (net (code "27") (name "Net-(D7-IF)") (class "Default")
      (node (ref "D7") (pin "2") (pinfunction "IF_2") (pintype "passive"))
      (node (ref "Z4") (pin "2") (pinfunction "2_2") (pintype "bidirectional"))
    )
    (net (code "28") (name "Net-(D7-RF)") (class "Default")
      (node (ref "D7") (pin "4") (pinfunction "RF_4") (pintype "passive"))
      (node (ref "Z3") (pin "2") (pinfunction "2_2") (pintype "bidirectional"))
    )
    (net (code "29") (name "Net-(D8A-RFC)") (class "Default")
      (node (ref "D8") (pin "7") (pinfunction "RFC_7") (pintype "passive"))
      (node (ref "Z4") (pin "4") (pinfunction "4_4") (pintype "bidirectional"))
    )
    (net (code "30") (name "Net-(D9A-RFC)") (class "Default")
      (node (ref "C24") (pin "2") (pinfunction "2_2") (pintype "passive"))
      (node (ref "D9") (pin "22") (pinfunction "RFC_22") (pintype "passive"))
    )
    (net (code "31") (name "Net-(D10-RFOUT)") (class "Default")
      (node (ref "C24") (pin "1") (pinfunction "1_1") (pintype "passive"))
      (node (ref "D10") (pin "16") (pinfunction "RFOUT_16") (pintype "passive"))
    )
    (net (code "32") (name "Net-(D11-IN)") (class "Default")
      (node (ref "C49") (pin "2") (pinfunction "2_2") (pintype "passive"))
      (node (ref "D11") (pin "1") (pinfunction "IN_1") (pintype "passive"))
    )
    (net (code "33") (name "Net-(D11-OUT)") (class "Default")
      (node (ref "C45") (pin "1") (pinfunction "1_1") (pintype "passive"))
      (node (ref "D11") (pin "3") (pinfunction "OUT_3") (pintype "passive"))
      (node (ref "L15") (pin "1") (pinfunction "1_1") (pintype "passive"))
    )
    (net (code "34") (name "Net-(D12A-CMa)") (class "Default")
      (node (ref "C54") (pin "2") (pinfunction "2_2") (pintype "passive"))
      (node (ref "D12") (pin "16") (pinfunction "TB_16") (pintype "passive"))
      (node (ref "D12") (pin "18") (pinfunction "CMc_18") (pintype "passive"))
      (node (ref "D12") (pin "19") (pinfunction "CMb_19") (pintype "passive"))
      (node (ref "D12") (pin "20") (pinfunction "CMa_20") (pintype "passive"))
    )
    (net (code "35") (name "Net-(D12A-CP)") (class "Default")
      (node (ref "C56") (pin "2") (pinfunction "2_2") (pintype "passive"))
      (node (ref "D12") (pin "15") (pinfunction "TUNE_15") (pintype "passive"))
      (node (ref "D12") (pin "26") (pinfunction "CP_26") (pintype "passive"))
      (node (ref "R25") (pin "1") (pinfunction "1_1") (pintype "passive"))
    )
    (net (code "36") (name "Net-(D12A-REF-)") (class "Default")
      (node (ref "C55") (pin "1") (pinfunction "1_1") (pintype "passive"))
      (node (ref "D12") (pin "28") (pinfunction "REF-_28") (pintype "passive"))
      (node (ref "R24") (pin "2") (pinfunction "2_2") (pintype "passive"))
    )
    (net (code "37") (name "Net-(D13A-CMa)") (class "Default")
      (node (ref "C68") (pin "2") (pinfunction "2_2") (pintype "passive"))
      (node (ref "D13") (pin "16") (pinfunction "TB_16") (pintype "passive"))
      (node (ref "D13") (pin "18") (pinfunction "CMc_18") (pintype "passive"))
      (node (ref "D13") (pin "19") (pinfunction "CMb_19") (pintype "passive"))
      (node (ref "D13") (pin "20") (pinfunction "CMa_20") (pintype "passive"))
    )
    (net (code "38") (name "Net-(D13A-CP)") (class "Default")
      (node (ref "C70") (pin "2") (pinfunction "2_2") (pintype "passive"))
      (node (ref "D13") (pin "15") (pinfunction "TUNE_15") (pintype "passive"))
      (node (ref "D13") (pin "26") (pinfunction "CP_26") (pintype "passive"))
      (node (ref "R28") (pin "1") (pinfunction "1_1") (pintype "passive"))
    )
    (net (code "39") (name "Net-(D13A-REF-)") (class "Default")
      (node (ref "C69") (pin "1") (pinfunction "1_1") (pintype "passive"))
      (node (ref "D13") (pin "28") (pinfunction "REF-_28") (pintype "passive"))
      (node (ref "R27") (pin "2") (pinfunction "2_2") (pintype "passive"))
    )
    (net (code "40") (name "Net-(D13A-RF+)") (class "Default")
      (node (ref "C66") (pin "1") (pinfunction "1_1") (pintype "passive"))
      (node (ref "D13") (pin "12") (pinfunction "RF+_12") (pintype "passive"))
      (node (ref "L16") (pin "1") (pinfunction "1_1") (pintype "passive"))
    )
    (net (code "41") (name "Net-(D13A-RF-)") (class "Default")
      (node (ref "C67") (pin "1") (pinfunction "1_1") (pintype "passive"))
      (node (ref "D13") (pin "11") (pinfunction "RF-_11") (pintype "passive"))
      (node (ref "L17") (pin "1") (pinfunction "1_1") (pintype "passive"))
    )
    (net (code "42") (name "Net-(R13-Pad2)") (class "Default")
      (node (ref "R13") (pin "2") (pinfunction "2_2") (pintype "passive"))
      (node (ref "Z3") (pin "4") (pinfunction "4_4") (pintype "bidirectional"))
    )
    (net (code "43") (name "Net-(R14-Pad2)") (class "Default")
      (node (ref "R14") (pin "2") (pinfunction "2_2") (pintype "passive"))
      (node (ref "Z4") (pin "6") (pinfunction "6_6") (pintype "bidirectional"))
    )
    (net (code "44") (name "Net-(T2-Pad6)") (class "Default")
      (node (ref "T2") (pin "6") (pinfunction "6_6") (pintype "passive"))
      (node (ref "Z5") (pin "OUT") (pinfunction "OUT_OUT") (pintype "passive"))
    )
    (net (code "45") (name "Net-(T3-Pad4)") (class "Default")
      (node (ref "T3") (pin "4") (pinfunction "4_4") (pintype "passive"))
      (node (ref "Z5") (pin "IN") (pinfunction "IN_IN") (pintype "passive"))
    )
    (net (code "46") (name "QMOD_DSOP") (class "Default")
      (node (ref "D10") (pin "1") (pinfunction "DSOP_1") (pintype "passive"))
    )
    (net (code "47") (name "TX_IOUTA_N") (class "Default")
      (node (ref "C40") (pin "2") (pinfunction "2_2") (pintype "passive"))
      (node (ref "L14") (pin "1") (pinfunction "1_1") (pintype "passive"))
      (node (ref "R20") (pin "2") (pinfunction "2_2") (pintype "passive"))
    )
    (net (code "48") (name "TX_IOUTA_P") (class "Default")
      (node (ref "C40") (pin "1") (pinfunction "1_1") (pintype "passive"))
      (node (ref "L13") (pin "1") (pinfunction "1_1") (pintype "passive"))
      (node (ref "R19") (pin "1") (pinfunction "1_1") (pintype "passive"))
    )
    (net (code "49") (name "TX_IOUTB_N") (class "Default")
      (node (ref "C34") (pin "2") (pinfunction "2_2") (pintype "passive"))
      (node (ref "L10") (pin "1") (pinfunction "1_1") (pintype "passive"))
      (node (ref "R17") (pin "2") (pinfunction "2_2") (pintype "passive"))
    )
    (net (code "50") (name "TX_IOUTB_P") (class "Default")
      (node (ref "C34") (pin "1") (pinfunction "1_1") (pintype "passive"))
      (node (ref "L9") (pin "1") (pinfunction "1_1") (pintype "passive"))
      (node (ref "R16") (pin "1") (pinfunction "1_1") (pintype "passive"))
    )
    (net (code "51") (name "_LO1_TX_n") (class "Default")
      (node (ref "D12") (pin "11") (pinfunction "RF-_11") (pintype "passive"))
      (node (ref "T1") (pin "4") (pinfunction "4_4") (pintype "passive"))
    )
    (net (code "52") (name "_LO1_TX_p") (class "Default")
      (node (ref "D12") (pin "12") (pinfunction "RF+_12") (pintype "passive"))
      (node (ref "T1") (pin "6") (pinfunction "6_6") (pintype "passive"))
    )
    (net (code "53") (name "_iouta_qmod_n") (class "Default")
      (node (ref "C35") (pin "2") (pinfunction "2_2") (pintype "passive"))
      (node (ref "C37") (pin "2") (pinfunction "2_2") (pintype "passive"))
      (node (ref "D10") (pin "22") (pinfunction "IBBN_22") (pintype "passive"))
      (node (ref "L12") (pin "2") (pinfunction "2_2") (pintype "passive"))
      (node (ref "R18") (pin "2") (pinfunction "2_2") (pintype "passive"))
    )
    (net (code "54") (name "_iouta_qmod_p") (class "Default")
      (node (ref "C35") (pin "1") (pinfunction "1_1") (pintype "passive"))
      (node (ref "C36") (pin "1") (pinfunction "1_1") (pintype "passive"))
      (node (ref "D10") (pin "21") (pinfunction "IBBP_21") (pintype "passive"))
      (node (ref "L11") (pin "2") (pinfunction "2_2") (pintype "passive"))
      (node (ref "R18") (pin "1") (pinfunction "1_1") (pintype "passive"))
    )
    (net (code "55") (name "_ioutb_qmod_n") (class "Default")
      (node (ref "C29") (pin "2") (pinfunction "2_2") (pintype "passive"))
      (node (ref "C31") (pin "2") (pinfunction "2_2") (pintype "passive"))
      (node (ref "D10") (pin "9") (pinfunction "QBBN_9") (pintype "passive"))
      (node (ref "L8") (pin "2") (pinfunction "2_2") (pintype "passive"))
      (node (ref "R15") (pin "2") (pinfunction "2_2") (pintype "passive"))
    )
    (net (code "56") (name "_ioutb_qmod_p") (class "Default")
      (node (ref "C29") (pin "1") (pinfunction "1_1") (pintype "passive"))
      (node (ref "C30") (pin "1") (pinfunction "1_1") (pintype "passive"))
      (node (ref "D10") (pin "10") (pinfunction "QBBP_10") (pintype "passive"))
      (node (ref "L7") (pin "2") (pinfunction "2_2") (pintype "passive"))
      (node (ref "R15") (pin "1") (pinfunction "1_1") (pintype "passive"))
    )
    (net (code "57") (name "lo1_ref_tx") (class "Default")
      (node (ref "C41") (pin "1") (pinfunction "1_1") (pintype "passive"))
      (node (ref "D12") (pin "1") (pinfunction "REF+_1") (pintype "passive"))
      (node (ref "R24") (pin "1") (pinfunction "1_1") (pintype "passive"))
    )
    (net (code "58") (name "lo2_ref_tx") (class "Default")
      (node (ref "C42") (pin "1") (pinfunction "1_1") (pintype "passive"))
      (node (ref "D13") (pin "1") (pinfunction "REF+_1") (pintype "passive"))
      (node (ref "R27") (pin "1") (pinfunction "1_1") (pintype "passive"))
    )
    (net (code "59") (name "ref_freq_tx_n") (class "Default")
      (node (ref "C43") (pin "2") (pinfunction "2_2") (pintype "passive"))
    )
    (net (code "60") (name "ref_freq_tx_p") (class "Default")
      (node (ref "C44") (pin "2") (pinfunction "2_2") (pintype "passive"))
    )
    (net (code "61") (name "unconnected-(D10-NC-Pad6)") (class "Default")
      (node (ref "D10") (pin "6") (pinfunction "NC_6") (pintype "passive+no_connect"))
    )
    (net (code "62") (name "unconnected-(D10-NC-Pad7)") (class "Default")
      (node (ref "D10") (pin "7") (pinfunction "NC_7") (pintype "passive+no_connect"))
    )
    (net (code "63") (name "unconnected-(D10-NC-Pad13)") (class "Default")
      (node (ref "D10") (pin "13") (pinfunction "NC_13") (pintype "passive+no_connect"))
    )
    (net (code "64") (name "unconnected-(D10-NC-Pad15)") (class "Default")
      (node (ref "D10") (pin "15") (pinfunction "NC_15") (pintype "passive+no_connect"))
    )
  )
)
